# design.net
KiCad netlist of a schematic drawn in Altium Designer
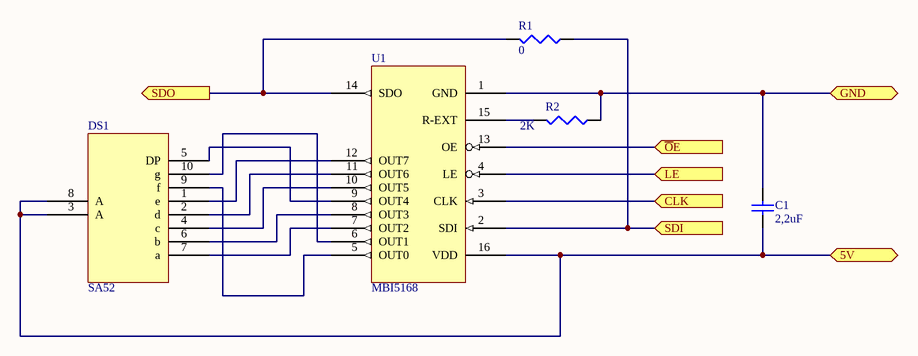
[diagram p0: Индикатор с драйвером.SchDoc]

(export (version "E")
  (design (tool "Eeschema 10.0.6"))
  (components
    (comp (ref "C1")
      (value "2,2uF")
      (footprint "CAPC1608L")
      (description "Capacitor (Semiconductor SIM Model)")
      (fields (field (name "Comment") "Cap Semi") (field (name "PUBLISHER") "Altium Limited"))
      (libsource (lib "Miscellaneous Devices") (part "Cap Semi"))
    )
    (comp (ref "DS1")
      (value "SA52")
      (footprint "LED52")
      (description "KingBright, SA23-11")
      (libsource (lib "LibX") (part "SA52-11"))
    )
    (comp (ref "R1")
      (value "0")
      (footprint "RESC1608L")
      (description "Resistor")
      (fields (field (name "PUBLISHER") "Altium Limited"))
      (libsource (lib "Miscellaneous Devices") (part "Res3"))
    )
    (comp (ref "R2")
      (value "2K")
      (footprint "RESC1608L")
      (description "Resistor")
      (fields (field (name "Comment") "Res3") (field (name "PUBLISHER") "Altium Limited"))
      (libsource (lib "Miscellaneous Devices") (part "Res3"))
    )
    (comp (ref "U1")
      (value "MBI5168")
      (footprint "SO-16_M")
      (description "Macroblock, 8-bit Constant Current LED Sink Driver")
      (libsource (lib "LibX") (part "MBI5168"))
    )
  )
  (nets
    (net (code "1") (name "/5V") (class "Default")
      (node (ref "C1") (pin "2") (pinfunction "2_2") (pintype "passive"))
      (node (ref "DS1") (pin "3") (pinfunction "A_3") (pintype "passive"))
      (node (ref "DS1") (pin "8") (pinfunction "A_8") (pintype "passive"))
      (node (ref "U1") (pin "16") (pinfunction "VDD_16") (pintype "power_in"))
    )
    (net (code "2") (name "/CLK") (class "Default")
      (node (ref "U1") (pin "3") (pinfunction "CLK_3") (pintype "input"))
    )
    (net (code "3") (name "/GND") (class "Default")
      (node (ref "C1") (pin "1") (pinfunction "1_1") (pintype "passive"))
      (node (ref "R2") (pin "1") (pinfunction "1_1") (pintype "passive"))
      (node (ref "U1") (pin "1") (pinfunction "GND_1") (pintype "power_in"))
    )
    (net (code "4") (name "/LE") (class "Default")
      (node (ref "U1") (pin "4") (pinfunction "LE_4") (pintype "input"))
    )
    (net (code "5") (name "/SDI") (class "Default")
      (node (ref "R1") (pin "1") (pinfunction "1_1") (pintype "passive"))
      (node (ref "U1") (pin "2") (pinfunction "SDI_2") (pintype "input"))
    )
    (net (code "6") (name "/SDO") (class "Default")
      (node (ref "R1") (pin "2") (pinfunction "2_2") (pintype "passive"))
      (node (ref "U1") (pin "14") (pinfunction "SDO_14") (pintype "output"))
    )
    (net (code "7") (name "/~{O}E") (class "Default")
      (node (ref "U1") (pin "13") (pinfunction "OE_13") (pintype "input"))
    )
    (net (code "8") (name "Net-(DS1-DP)") (class "Default")
      (node (ref "DS1") (pin "5") (pinfunction "DP_5") (pintype "passive"))
      (node (ref "U1") (pin "9") (pinfunction "OUT4_9") (pintype "output"))
    )
    (net (code "9") (name "Net-(DS1-a)") (class "Default")
      (node (ref "DS1") (pin "7") (pinfunction "a_7") (pintype "passive"))
      (node (ref "U1") (pin "7") (pinfunction "OUT2_7") (pintype "output"))
    )
    (net (code "10") (name "Net-(DS1-b)") (class "Default")
      (node (ref "DS1") (pin "6") (pinfunction "b_6") (pintype "passive"))
      (node (ref "U1") (pin "8") (pinfunction "OUT3_8") (pintype "output"))
    )
    (net (code "11") (name "Net-(DS1-c)") (class "Default")
      (node (ref "DS1") (pin "4") (pinfunction "c_4") (pintype "passive"))
      (node (ref "U1") (pin "10") (pinfunction "OUT5_10") (pintype "output"))
    )
    (net (code "12") (name "Net-(DS1-d)") (class "Default")
      (node (ref "DS1") (pin "2") (pinfunction "d_2") (pintype "passive"))
      (node (ref "U1") (pin "11") (pinfunction "OUT6_11") (pintype "output"))
    )
    (net (code "13") (name "Net-(DS1-e)") (class "Default")
      (node (ref "DS1") (pin "1") (pinfunction "e_1") (pintype "passive"))
      (node (ref "U1") (pin "12") (pinfunction "OUT7_12") (pintype "output"))
    )
    (net (code "14") (name "Net-(DS1-f)") (class "Default")
      (node (ref "DS1") (pin "9") (pinfunction "f_9") (pintype "passive"))
      (node (ref "U1") (pin "5") (pinfunction "OUT0_5") (pintype "output"))
    )
    (net (code "15") (name "Net-(DS1-g)") (class "Default")
      (node (ref "DS1") (pin "10") (pinfunction "g_10") (pintype "passive"))
      (node (ref "U1") (pin "6") (pinfunction "OUT1_6") (pintype "output"))
    )
    (net (code "16") (name "Net-(U1-R-EXT)") (class "Default")
      (node (ref "R2") (pin "2") (pinfunction "2_2") (pintype "passive"))
      (node (ref "U1") (pin "15") (pinfunction "R-EXT_15") (pintype "passive"))
    )
  )
)
